# 5v-high-power.net
KiCad netlist of a schematic drawn in EAGLE
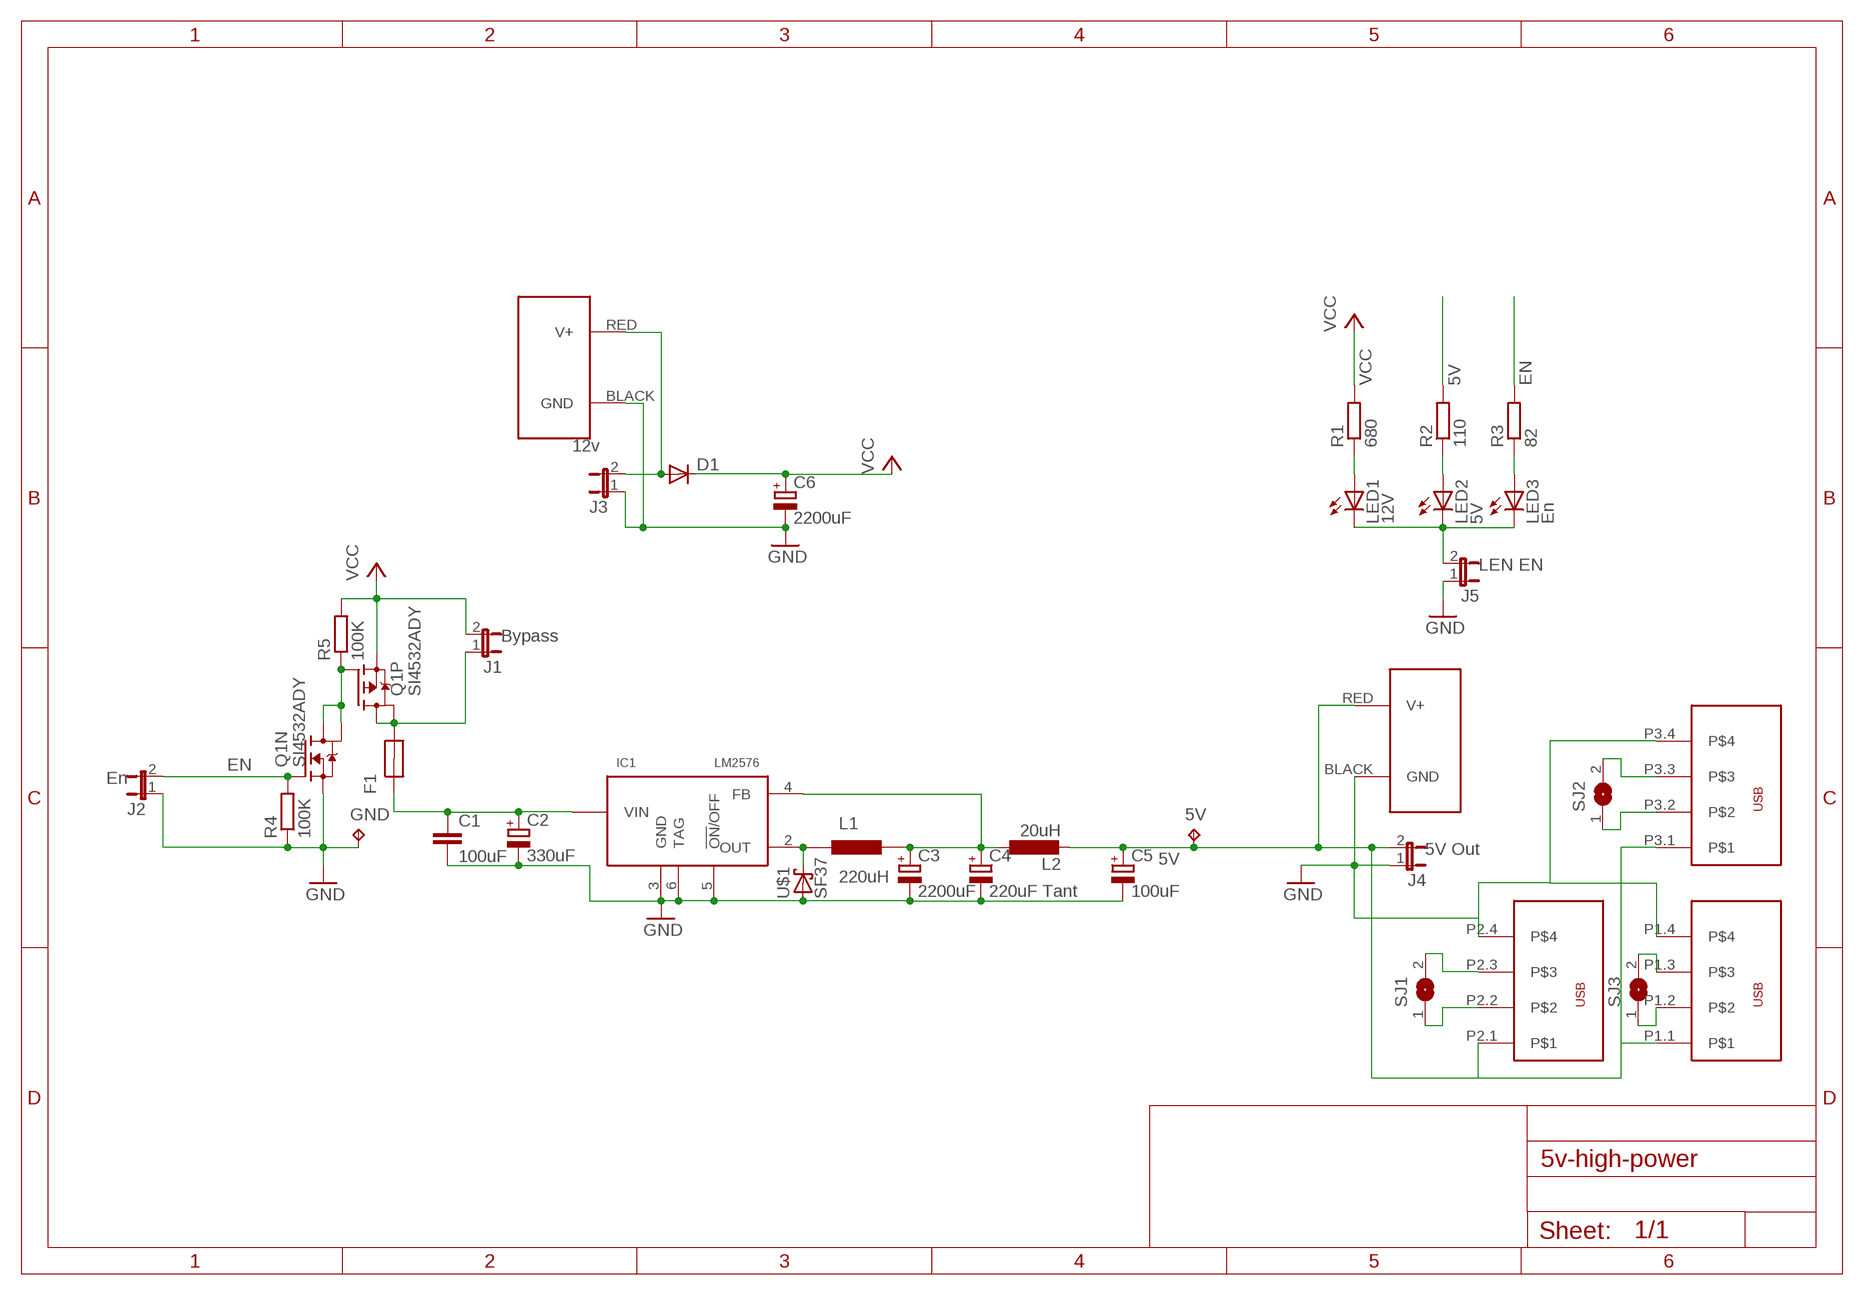
[diagram p0: schematic, sheet 1]

(export (version "E")
  (design (tool "Eeschema 10.0.6"))
  (components
    (comp (ref "5V")
      (value "5V B")
      (footprint "eagle-import:B1,27")
      (libsource (lib "eagle-import") (part "TPB1,27"))
    )
    (comp (ref "C1")
      (value "100uF")
      (footprint "eagle-import:C1210K")
      (libsource (lib "eagle-import") (part "C-EUC1210K"))
    )
    (comp (ref "C2")
      (value "330uF")
      (footprint "eagle-import:E5-8,5")
      (libsource (lib "eagle-import") (part "CPOL-EUE5-8.5"))
    )
    (comp (ref "C3")
      (value "2200uF")
      (footprint "eagle-import:E5-13")
      (libsource (lib "eagle-import") (part "CPOL-EUE5-13"))
    )
    (comp (ref "C4")
      (value "220uF Tant")
      (footprint "eagle-import:B_3528-21R")
      (libsource (lib "eagle-import") (part "CPOL-EUB/3528-21R"))
    )
    (comp (ref "C5")
      (value "100uF")
      (footprint "eagle-import:PANASONIC_E")
      (libsource (lib "eagle-import") (part "CPOL-EUE"))
    )
    (comp (ref "C6")
      (value "2200uF")
      (footprint "eagle-import:E5-13")
      (libsource (lib "eagle-import") (part "CPOL-EUE5-13"))
    )
    (comp (ref "D1")
      (value "DIODE-SMB")
      (footprint "eagle-import:SMB")
      (libsource (lib "eagle-import") (part "DIODE-SMB"))
    )
    (comp (ref "F1")
      (value "MF-MSMF110")
      (footprint "eagle-import:1812")
      (libsource (lib "eagle-import") (part "MF-MSMF110"))
    )
    (comp (ref "GND")
      (value "5V B")
      (footprint "eagle-import:B1,27")
      (libsource (lib "eagle-import") (part "TPB1,27"))
    )
    (comp (ref "IC1")
      (value "LM2576")
      (footprint "eagle-import:TO263")
      (libsource (lib "eagle-import") (part "LM2576"))
    )
    (comp (ref "J1")
      (value "Bypass")
      (footprint "eagle-import:2-MOLEX")
      (libsource (lib "eagle-import") (part "2-PIN-MOLEX"))
    )
    (comp (ref "J2")
      (value "En")
      (footprint "eagle-import:2-MOLEX")
      (libsource (lib "eagle-import") (part "2-PIN-MOLEX"))
    )
    (comp (ref "J3")
      (value "12v")
      (footprint "eagle-import:2-MOLEX")
      (libsource (lib "eagle-import") (part "2-PIN-MOLEX"))
    )
    (comp (ref "J4")
      (value "5V Out")
      (footprint "eagle-import:2-MOLEX")
      (libsource (lib "eagle-import") (part "2-PIN-MOLEX"))
    )
    (comp (ref "J5")
      (value "LEN EN")
      (footprint "eagle-import:2-MOLEX")
      (libsource (lib "eagle-import") (part "2-PIN-MOLEX"))
    )
    (comp (ref "J6")
      (value "POWERPOLE_POWER25A")
      (footprint "eagle-import:POWERPOLE_PAIR_25A")
      (libsource (lib "eagle-import") (part "POWERPOLE_POWER25A"))
    )
    (comp (ref "J7")
      (value "POWERPOLE_POWER25A")
      (footprint "eagle-import:POWERPOLE_PAIR_25A")
      (libsource (lib "eagle-import") (part "POWERPOLE_POWER25A"))
    )
    (comp (ref "L1")
      (value "220uH")
      (footprint "eagle-import:DR127")
      (libsource (lib "eagle-import") (part "DR127-221-R"))
    )
    (comp (ref "L2")
      (value "20uH")
      (footprint "eagle-import:6000-XXXX-RC")
      (libsource (lib "eagle-import") (part "L-EU6000-XXX-RC"))
    )
    (comp (ref "LED1")
      (value "12V")
      (footprint "eagle-import:CHIP-LED0805")
      (libsource (lib "eagle-import") (part "LEDCHIP-LED0805"))
    )
    (comp (ref "LED2")
      (value "5V")
      (footprint "eagle-import:CHIP-LED0805")
      (libsource (lib "eagle-import") (part "LEDCHIP-LED0805"))
    )
    (comp (ref "LED3")
      (value "En")
      (footprint "eagle-import:CHIP-LED0805")
      (libsource (lib "eagle-import") (part "LEDCHIP-LED0805"))
    )
    (comp (ref "Q1")
      (value "SI4532ADY")
      (footprint "eagle-import:SO8")
      (libsource (lib "eagle-import") (part "SI4532ADY"))
    )
    (comp (ref "R1")
      (value "680")
      (footprint "eagle-import:R0805")
      (libsource (lib "eagle-import") (part "R-EU_R0805"))
    )
    (comp (ref "R2")
      (value "110")
      (footprint "eagle-import:R0805")
      (libsource (lib "eagle-import") (part "R-EU_R0805"))
    )
    (comp (ref "R3")
      (value "82")
      (footprint "eagle-import:R0805")
      (libsource (lib "eagle-import") (part "R-EU_R0805"))
    )
    (comp (ref "R4")
      (value "100K")
      (footprint "eagle-import:R0805")
      (libsource (lib "eagle-import") (part "R-EU_R0805"))
    )
    (comp (ref "R5")
      (value "100K")
      (footprint "eagle-import:R0805")
      (libsource (lib "eagle-import") (part "R-EU_R0805"))
    )
    (comp (ref "SJ1") (value "SJ") (footprint "eagle-import:SJ") (libsource (lib "eagle-import") (part "SJ")))
    (comp (ref "SJ2") (value "SJ") (footprint "eagle-import:SJ") (libsource (lib "eagle-import") (part "SJ")))
    (comp (ref "SJ3") (value "SJ") (footprint "eagle-import:SJ") (libsource (lib "eagle-import") (part "SJ")))
    (comp (ref "U$1")
      (value "SF37")
      (footprint "eagle-import:DO-201AD")
      (libsource (lib "eagle-import") (part "SF37"))
    )
    (comp (ref "U$2")
      (value "USB_DUAL_VERT+HORIZTRIPPLE")
      (footprint "eagle-import:USB_DUAL_HORIZ+VERT")
      (libsource (lib "eagle-import") (part "USB_DUAL_VERT+HORIZTRIPPLE"))
    )
  )
  (nets
    (net (code "1") (name "/5V") (class "Default")
      (node (ref "5V") (pin "TP") (pinfunction "TP_TP") (pintype "input"))
      (node (ref "C5") (pin "+") (pinfunction "+_+") (pintype "passive"))
      (node (ref "J4") (pin "2") (pinfunction "2_2") (pintype "passive"))
      (node (ref "J6") (pin "RED") (pinfunction "V+_RED") (pintype "power_in"))
      (node (ref "L2") (pin "2") (pinfunction "2_2") (pintype "passive"))
      (node (ref "R2") (pin "2") (pinfunction "2_2") (pintype "passive"))
      (node (ref "U$2") (pin "P1.1") (pinfunction "P$1_P1.1") (pintype "bidirectional"))
      (node (ref "U$2") (pin "P2.1") (pinfunction "P$1_P2.1") (pintype "bidirectional"))
      (node (ref "U$2") (pin "P3.1") (pinfunction "P$1_P3.1") (pintype "bidirectional"))
    )
    (net (code "2") (name "/EN") (class "Default")
      (node (ref "J2") (pin "2") (pinfunction "2_2") (pintype "passive"))
      (node (ref "Q1") (pin "2") (pinfunction "G_2") (pintype "passive"))
      (node (ref "R3") (pin "2") (pinfunction "2_2") (pintype "passive"))
      (node (ref "R4") (pin "2") (pinfunction "2_2") (pintype "passive"))
    )
    (net (code "3") (name "GND") (class "Default")
      (node (ref "C1") (pin "2") (pinfunction "2_2") (pintype "passive"))
      (node (ref "C2") (pin "-") (pinfunction "-_-") (pintype "passive"))
      (node (ref "C3") (pin "-") (pinfunction "-_-") (pintype "passive"))
      (node (ref "C4") (pin "-") (pinfunction "-_-") (pintype "passive"))
      (node (ref "C5") (pin "-") (pinfunction "-_-") (pintype "passive"))
      (node (ref "C6") (pin "-") (pinfunction "-_-") (pintype "passive"))
      (node (ref "GND") (pin "TP") (pinfunction "TP_TP") (pintype "input"))
      (node (ref "IC1") (pin "3") (pinfunction "GND_3") (pintype "power_in"))
      (node (ref "IC1") (pin "5") (pinfunction "~{ON}/OFF_5") (pintype "input"))
      (node (ref "IC1") (pin "6") (pinfunction "TAG_6") (pintype "power_in"))
      (node (ref "J2") (pin "1") (pinfunction "1_1") (pintype "passive"))
      (node (ref "J3") (pin "1") (pinfunction "1_1") (pintype "passive"))
      (node (ref "J4") (pin "1") (pinfunction "1_1") (pintype "passive"))
      (node (ref "J5") (pin "1") (pinfunction "1_1") (pintype "passive"))
      (node (ref "J6") (pin "BLACK") (pinfunction "GND_BLACK") (pintype "power_in"))
      (node (ref "J7") (pin "BLACK") (pinfunction "GND_BLACK") (pintype "power_in"))
      (node (ref "Q1") (pin "1") (pinfunction "S_1") (pintype "passive"))
      (node (ref "R4") (pin "1") (pinfunction "1_1") (pintype "passive"))
      (node (ref "U$1") (pin "2") (pinfunction "A_2") (pintype "passive"))
      (node (ref "U$2") (pin "P1.4") (pinfunction "P$4_P1.4") (pintype "bidirectional"))
      (node (ref "U$2") (pin "P2.4") (pinfunction "P$4_P2.4") (pintype "bidirectional"))
      (node (ref "U$2") (pin "P3.4") (pinfunction "P$4_P3.4") (pintype "bidirectional"))
    )
    (net (code "4") (name "Net-(F1-P$1)") (class "Default")
      (node (ref "C1") (pin "1") (pinfunction "1_1") (pintype "passive"))
      (node (ref "C2") (pin "+") (pinfunction "+_+") (pintype "passive"))
      (node (ref "F1") (pin "1") (pinfunction "P$1_1") (pintype "bidirectional"))
      (node (ref "IC1") (pin "1") (pinfunction "VIN_1") (pintype "power_in"))
    )
    (net (code "5") (name "Net-(F1-P$2)") (class "Default")
      (node (ref "F1") (pin "2") (pinfunction "P$2_2") (pintype "bidirectional"))
      (node (ref "J1") (pin "1") (pinfunction "1_1") (pintype "passive"))
      (node (ref "Q1") (pin "5") (pinfunction "D_5") (pintype "passive"))
      (node (ref "Q1") (pin "6") (pinfunction "D_6") (pintype "passive"))
    )
    (net (code "6") (name "Net-(IC1-FB)") (class "Default")
      (node (ref "C3") (pin "+") (pinfunction "+_+") (pintype "passive"))
      (node (ref "C4") (pin "+") (pinfunction "+_+") (pintype "passive"))
      (node (ref "IC1") (pin "4") (pinfunction "FB_4") (pintype "passive"))
      (node (ref "L1") (pin "2") (pinfunction "P$2_2") (pintype "bidirectional"))
      (node (ref "L2") (pin "1") (pinfunction "1_1") (pintype "passive"))
    )
    (net (code "7") (name "Net-(IC1-OUT)") (class "Default")
      (node (ref "IC1") (pin "2") (pinfunction "OUT_2") (pintype "output"))
      (node (ref "L1") (pin "1") (pinfunction "P$1_1") (pintype "bidirectional"))
      (node (ref "U$1") (pin "1") (pinfunction "C_1") (pintype "passive"))
    )
    (net (code "8") (name "Net-(J5-Pad2)") (class "Default")
      (node (ref "J5") (pin "2") (pinfunction "2_2") (pintype "passive"))
      (node (ref "LED1") (pin "C") (pinfunction "C_C") (pintype "passive"))
      (node (ref "LED2") (pin "C") (pinfunction "C_C") (pintype "passive"))
      (node (ref "LED3") (pin "C") (pinfunction "C_C") (pintype "passive"))
    )
    (net (code "9") (name "Net-(J7-V+)") (class "Default")
      (node (ref "D1") (pin "A") (pinfunction "A_A") (pintype "passive"))
      (node (ref "J3") (pin "2") (pinfunction "2_2") (pintype "passive"))
      (node (ref "J7") (pin "RED") (pinfunction "V+_RED") (pintype "power_in"))
    )
    (net (code "10") (name "Net-(LED1-PadA)") (class "Default")
      (node (ref "LED1") (pin "A") (pinfunction "A_A") (pintype "passive"))
      (node (ref "R1") (pin "1") (pinfunction "1_1") (pintype "passive"))
    )
    (net (code "11") (name "Net-(LED2-PadA)") (class "Default")
      (node (ref "LED2") (pin "A") (pinfunction "A_A") (pintype "passive"))
      (node (ref "R2") (pin "1") (pinfunction "1_1") (pintype "passive"))
    )
    (net (code "12") (name "Net-(LED3-PadA)") (class "Default")
      (node (ref "LED3") (pin "A") (pinfunction "A_A") (pintype "passive"))
      (node (ref "R3") (pin "1") (pinfunction "1_1") (pintype "passive"))
    )
    (net (code "13") (name "Net-(Q1B-G)") (class "Default")
      (node (ref "Q1") (pin "4") (pinfunction "G_4") (pintype "passive"))
      (node (ref "Q1") (pin "7") (pinfunction "D_7") (pintype "passive"))
      (node (ref "Q1") (pin "8") (pinfunction "D_8") (pintype "passive"))
      (node (ref "R5") (pin "1") (pinfunction "1_1") (pintype "passive"))
    )
    (net (code "14") (name "Net-(U$2A-P$2)") (class "Default")
      (node (ref "SJ3") (pin "1") (pinfunction "1_1") (pintype "passive"))
      (node (ref "U$2") (pin "P1.2") (pinfunction "P$2_P1.2") (pintype "bidirectional"))
    )
    (net (code "15") (name "Net-(U$2A-P$3)") (class "Default")
      (node (ref "SJ3") (pin "2") (pinfunction "2_2") (pintype "passive"))
      (node (ref "U$2") (pin "P1.3") (pinfunction "P$3_P1.3") (pintype "bidirectional"))
    )
    (net (code "16") (name "Net-(U$2B-P$2)") (class "Default")
      (node (ref "SJ1") (pin "1") (pinfunction "1_1") (pintype "passive"))
      (node (ref "U$2") (pin "P2.2") (pinfunction "P$2_P2.2") (pintype "bidirectional"))
    )
    (net (code "17") (name "Net-(U$2B-P$3)") (class "Default")
      (node (ref "SJ1") (pin "2") (pinfunction "2_2") (pintype "passive"))
      (node (ref "U$2") (pin "P2.3") (pinfunction "P$3_P2.3") (pintype "bidirectional"))
    )
    (net (code "18") (name "Net-(U$2C-P$2)") (class "Default")
      (node (ref "SJ2") (pin "1") (pinfunction "1_1") (pintype "passive"))
      (node (ref "U$2") (pin "P3.2") (pinfunction "P$2_P3.2") (pintype "bidirectional"))
    )
    (net (code "19") (name "Net-(U$2C-P$3)") (class "Default")
      (node (ref "SJ2") (pin "2") (pinfunction "2_2") (pintype "passive"))
      (node (ref "U$2") (pin "P3.3") (pinfunction "P$3_P3.3") (pintype "bidirectional"))
    )
    (net (code "20") (name "VCC") (class "Default")
      (node (ref "C6") (pin "+") (pinfunction "+_+") (pintype "passive"))
      (node (ref "D1") (pin "C") (pinfunction "C_C") (pintype "passive"))
      (node (ref "J1") (pin "2") (pinfunction "2_2") (pintype "passive"))
      (node (ref "Q1") (pin "3") (pinfunction "S_3") (pintype "passive"))
      (node (ref "R1") (pin "2") (pinfunction "2_2") (pintype "passive"))
      (node (ref "R5") (pin "2") (pinfunction "2_2") (pintype "passive"))
    )
  )
)
